# IM69D130_MEMS_Microphone.net
KiCad netlist of a schematic drawn in Altium Designer
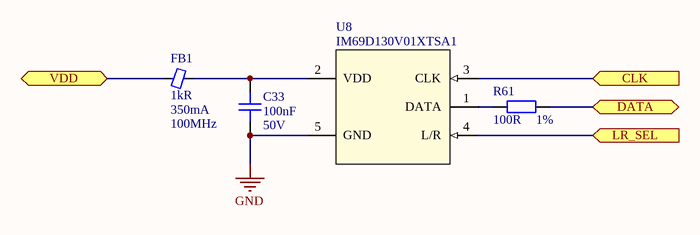
[diagram p0: IM69D130_MEMS_Microphone.SchDoc]

(export (version "E")
  (design (tool "Eeschema 10.0.6"))
  (components
    (comp (ref "C33")
      (value "CAP CER 0.1UF 50V X7R 0402")
      (footprint "C0402")
      (description "0.1µF ±10% 50V Ceramic Capacitor X7R 0402 (1005 Metric)")
      (fields
        (field (name "MANUFACTURER") "TDK")
        (field (name "MANUFACTURER PART NUMBER") "CGA2B3X7R1H104K050BB")
        (field (name "CAPACITANCE") "100nF")
        (field (name "VOLTAGE") "50V")
      )
      (libsource (lib "capacitors_smd") (part "CAP CER 0.1UF 50V X7R 0402"))
    )
    (comp (ref "FB1")
      (value "FERRITE BEAD 1 KOHM 0402 1LN")
      (footprint "L_0402")
      (description "1 kOhms @ 100MHz 1  Ferrite Bead 0402 (1005 Metric) 350mA 490mOhm")
      (fields
        (field (name "MANUFACTURER") "Murata")
        (field (name "MANUFACTURER PART NUMBER") "BLM15AX102SN1D")
        (field (name "IMPEDANCE") "1kR")
        (field (name "MAX DC CURRENT") "350mA")
        (field (name "TEST FREQUENCY") "100MHz")
      )
      (libsource (lib "ferrite_beads") (part "FERRITE BEAD 1 KOHM 0402 1LN"))
    )
    (comp (ref "R61")
      (value "RES SMD 100 OHM 1% 1/16W 0402")
      (footprint "0402R")
      (description "100 Ohms ±1% 0.063W, 1/16W Chip Resistor 0402 (1005 Metric) Moisture Resistant Thick Film")
      (fields
        (field (name "MANUFACTURER") "Yageo")
        (field (name "MANUFACTURER PART NUMBER") "RC0402FR-07100RL")
        (field (name "TOLERANCE") "1%")
        (field (name "RESISTANCE") "100R")
      )
      (libsource (lib "resistors_smd") (part "RES SMD 100 OHM 1% 1/16W 0402"))
    )
    (comp (ref "U8")
      (value "IM69D130V01XTSA1")
      (footprint "MIC_IM69D130V01XTSA1")
      (fields (field (name "MANUFACTURER") "Infineon"))
      (libsource (lib "BLDC_Motor_Driver") (part "IC IM69D130 MICROPHONE MEMS DIGITAL PDM OMNI"))
    )
  )
  (nets
    (net (code "1") (name "/CLK") (class "Default")
      (node (ref "U8") (pin "3") (pinfunction "CLK_3") (pintype "input"))
    )
    (net (code "2") (name "/DATA") (class "Default")
      (node (ref "R61") (pin "1") (pinfunction "1_1") (pintype "passive"))
    )
    (net (code "3") (name "/LR_SEL") (class "Default")
      (node (ref "U8") (pin "4") (pinfunction "L/R_4") (pintype "input"))
    )
    (net (code "4") (name "/VDD") (class "Default")
      (node (ref "FB1") (pin "1") (pinfunction "1_1") (pintype "passive"))
    )
    (net (code "5") (name "GND") (class "Default")
      (node (ref "C33") (pin "1") (pinfunction "1_1") (pintype "passive"))
      (node (ref "U8") (pin "5") (pinfunction "GND_5") (pintype "power_in"))
    )
    (net (code "6") (name "Net-(U8-DATA)") (class "Default")
      (node (ref "R61") (pin "2") (pinfunction "2_2") (pintype "passive"))
      (node (ref "U8") (pin "1") (pinfunction "DATA_1") (pintype "tri_state"))
    )
    (net (code "7") (name "Net-(U8-VDD)") (class "Default")
      (node (ref "C33") (pin "2") (pinfunction "2_2") (pintype "passive"))
      (node (ref "FB1") (pin "2") (pinfunction "2_2") (pintype "passive"))
      (node (ref "U8") (pin "2") (pinfunction "VDD_2") (pintype "power_in"))
    )
  )
)
